# V0p2_Main_PCB2.net
KiCad netlist of a schematic drawn in EAGLE
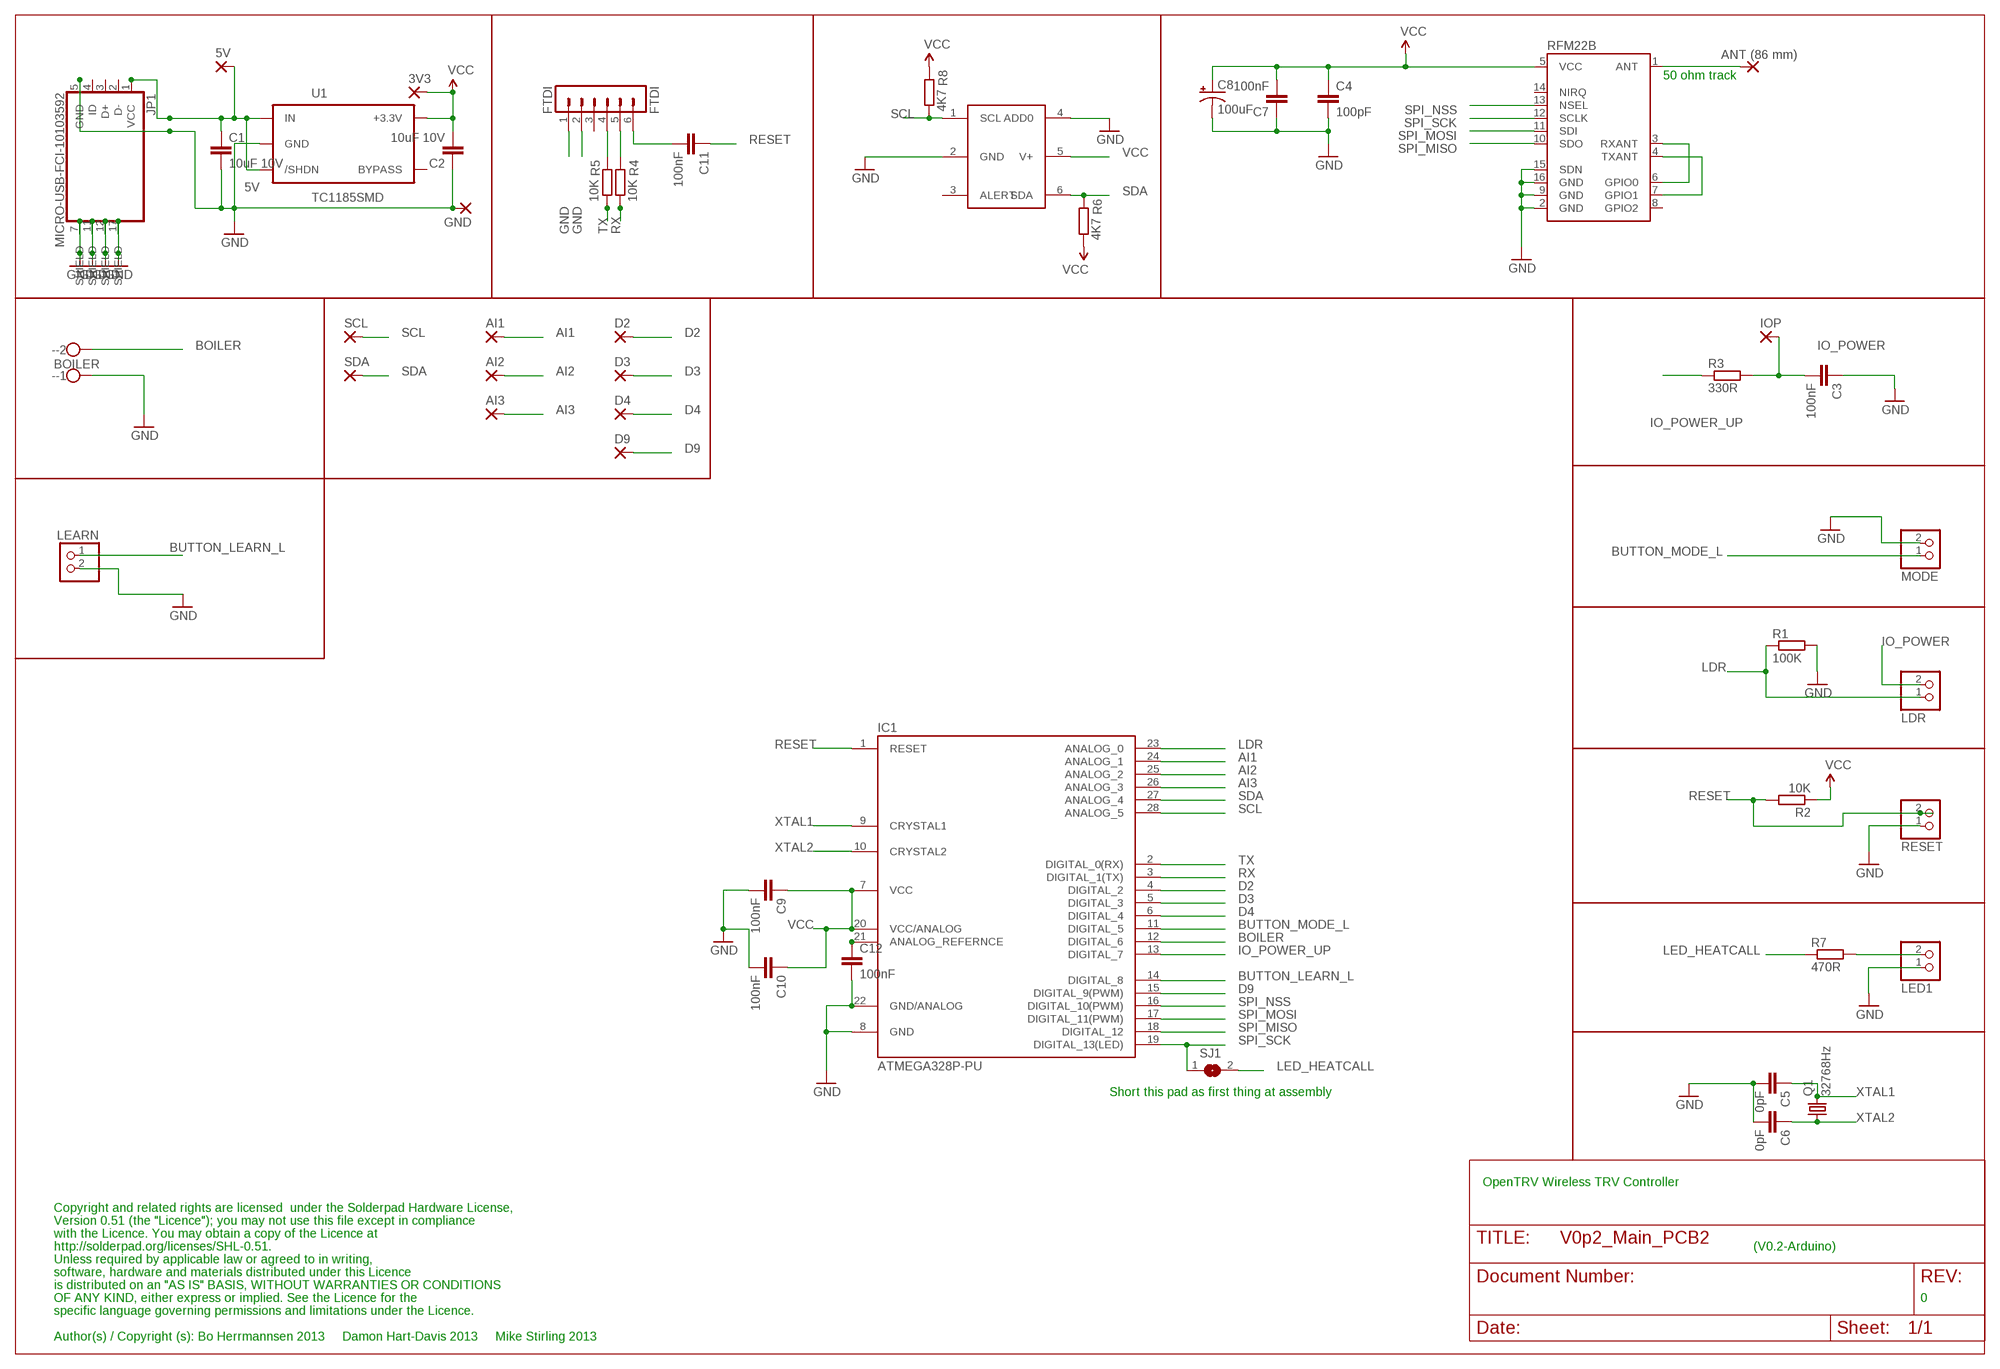
[diagram p0: schematic, sheet 1]

(export (version "E")
  (design (tool "Eeschema 10.0.6"))
  (components
    (comp (ref "-")
      (value "BOILER")
      (footprint "eagle-import:SCREWTERMINAL")
      (fields (field (name "MPN") "237-102"))
      (libsource (lib "eagle-import") (part "W237-102"))
    )
    (comp (ref "3V3")
      (value "2,15/1,0")
      (footprint "eagle-import:2,15_1,0")
      (libsource (lib "eagle-import") (part "2,15/1,0"))
    )
    (comp (ref "5V")
      (value "2,15/1,0")
      (footprint "eagle-import:2,15_1,0")
      (libsource (lib "eagle-import") (part "2,15/1,0"))
    )
    (comp (ref "AI1")
      (value "2,15/1,0")
      (footprint "eagle-import:2,15_1,0")
      (libsource (lib "eagle-import") (part "2,15/1,0"))
    )
    (comp (ref "AI2")
      (value "2,15/1,0")
      (footprint "eagle-import:2,15_1,0")
      (libsource (lib "eagle-import") (part "2,15/1,0"))
    )
    (comp (ref "AI3")
      (value "2,15/1,0")
      (footprint "eagle-import:2,15_1,0")
      (libsource (lib "eagle-import") (part "2,15/1,0"))
    )
    (comp (ref "ANT")
      (value "ANT (86 mm)")
      (footprint "eagle-import:2,15_1,0")
      (libsource (lib "eagle-import") (part "2,15/1,0"))
    )
    (comp (ref "C1")
      (value "10uF 10V")
      (footprint "eagle-import:0603-CAP")
      (libsource (lib "eagle-import") (part "CAP0603-CAP"))
    )
    (comp (ref "C2")
      (value "10uF 10V")
      (footprint "eagle-import:0603-CAP")
      (libsource (lib "eagle-import") (part "CAP0603-CAP"))
    )
    (comp (ref "C3")
      (value "100nF")
      (footprint "eagle-import:0603-CAP")
      (libsource (lib "eagle-import") (part "CAP0603-CAP"))
    )
    (comp (ref "C4")
      (value "100pF")
      (footprint "eagle-import:0603-CAP")
      (libsource (lib "eagle-import") (part "CAP0603-CAP"))
    )
    (comp (ref "C5")
      (value "0pF")
      (footprint "eagle-import:0603-CAP")
      (libsource (lib "eagle-import") (part "CAP0603-CAP"))
    )
    (comp (ref "C6")
      (value "0pF")
      (footprint "eagle-import:0603-CAP")
      (libsource (lib "eagle-import") (part "CAP0603-CAP"))
    )
    (comp (ref "C7")
      (value "100nF")
      (footprint "eagle-import:0603-CAP")
      (libsource (lib "eagle-import") (part "CAP0603-CAP"))
    )
    (comp (ref "C8")
      (value "100uF")
      (footprint "eagle-import:EIA3216")
      (libsource (lib "eagle-import") (part "CAP_POL1206"))
    )
    (comp (ref "C9")
      (value "100nF")
      (footprint "eagle-import:0603-CAP")
      (libsource (lib "eagle-import") (part "CAP0603-CAP"))
    )
    (comp (ref "C10")
      (value "100nF")
      (footprint "eagle-import:0603-CAP")
      (libsource (lib "eagle-import") (part "CAP0603-CAP"))
    )
    (comp (ref "C11")
      (value "100nF")
      (footprint "eagle-import:0603-CAP")
      (libsource (lib "eagle-import") (part "CAP0603-CAP"))
    )
    (comp (ref "C12")
      (value "100nF")
      (footprint "eagle-import:0603-CAP")
      (libsource (lib "eagle-import") (part "CAP0603-CAP"))
    )
    (comp (ref "D2")
      (value "2,15/1,0")
      (footprint "eagle-import:2,15_1,0")
      (libsource (lib "eagle-import") (part "2,15/1,0"))
    )
    (comp (ref "D3")
      (value "2,15/1,0")
      (footprint "eagle-import:2,15_1,0")
      (libsource (lib "eagle-import") (part "2,15/1,0"))
    )
    (comp (ref "D4")
      (value "2,15/1,0")
      (footprint "eagle-import:2,15_1,0")
      (libsource (lib "eagle-import") (part "2,15/1,0"))
    )
    (comp (ref "D9")
      (value "2,15/1,0")
      (footprint "eagle-import:2,15_1,0")
      (libsource (lib "eagle-import") (part "2,15/1,0"))
    )
    (comp (ref "FTDI")
      (value "FTDI")
      (footprint "eagle-import:MA06-1")
      (libsource (lib "eagle-import") (part "MA06-1"))
    )
    (comp (ref "GND")
      (value "2,15/1,0")
      (footprint "eagle-import:2,15_1,0")
      (libsource (lib "eagle-import") (part "2,15/1,0"))
    )
    (comp (ref "IC1")
      (value "ATMEGA328P-PU")
      (footprint "eagle-import:DIL28-3")
      (libsource (lib "eagle-import") (part "ATMEGA8-PU"))
    )
    (comp (ref "IOP")
      (value "2,15/1,0")
      (footprint "eagle-import:2,15_1,0")
      (libsource (lib "eagle-import") (part "2,15/1,0"))
    )
    (comp (ref "JP1")
      (value "MICRO-USB-FCI-10103592")
      (footprint "eagle-import:MICRO-USB-FCI-10103592")
      (libsource (lib "eagle-import") (part "MICRO-USB-FCI-10103592"))
    )
    (comp (ref "LDR")
      (value "PINHD-1X2")
      (footprint "eagle-import:1X02")
      (libsource (lib "eagle-import") (part "PINHD-1X2"))
    )
    (comp (ref "LEARN")
      (value "PINHD-1X2")
      (footprint "eagle-import:1X02")
      (libsource (lib "eagle-import") (part "PINHD-1X2"))
    )
    (comp (ref "LED1")
      (value "PINHD-1X2")
      (footprint "eagle-import:1X02")
      (libsource (lib "eagle-import") (part "PINHD-1X2"))
    )
    (comp (ref "MODE")
      (value "PINHD-1X2")
      (footprint "eagle-import:1X02")
      (libsource (lib "eagle-import") (part "PINHD-1X2"))
    )
    (comp (ref "Q1")
      (value "32768Hz")
      (footprint "eagle-import:MC-306")
      (fields (field (name "MPN") "MC-306 60.0KHZ  100PPM ,12.5PF"))
      (libsource (lib "eagle-import") (part "MC-306"))
    )
    (comp (ref "R1")
      (value "100K")
      (footprint "eagle-import:R0603")
      (libsource (lib "eagle-import") (part "R-EU_R0603"))
    )
    (comp (ref "R2")
      (value "10K")
      (footprint "eagle-import:R0603")
      (libsource (lib "eagle-import") (part "R-EU_R0603"))
    )
    (comp (ref "R3")
      (value "330R")
      (footprint "eagle-import:R0603")
      (libsource (lib "eagle-import") (part "R-EU_R0603"))
    )
    (comp (ref "R4")
      (value "10K")
      (footprint "eagle-import:R0603")
      (libsource (lib "eagle-import") (part "R-EU_R0603"))
    )
    (comp (ref "R5")
      (value "10K")
      (footprint "eagle-import:R0603")
      (libsource (lib "eagle-import") (part "R-EU_R0603"))
    )
    (comp (ref "R6")
      (value "4K7")
      (footprint "eagle-import:R0603")
      (libsource (lib "eagle-import") (part "R-EU_R0603"))
    )
    (comp (ref "R7")
      (value "470R")
      (footprint "eagle-import:R0603")
      (libsource (lib "eagle-import") (part "R-EU_R0603"))
    )
    (comp (ref "R8")
      (value "4K7")
      (footprint "eagle-import:R0603")
      (libsource (lib "eagle-import") (part "R-EU_R0603"))
    )
    (comp (ref "RESET")
      (value "PINHD-1X2")
      (footprint "eagle-import:1X02")
      (libsource (lib "eagle-import") (part "PINHD-1X2"))
    )
    (comp (ref "RFM22B")
      (value "RFM22SMD")
      (footprint "eagle-import:RFM22-XXX-S2")
      (libsource (lib "eagle-import") (part "RFM22SMD"))
    )
    (comp (ref "SCL")
      (value "2,15/1,0")
      (footprint "eagle-import:2,15_1,0")
      (libsource (lib "eagle-import") (part "2,15/1,0"))
    )
    (comp (ref "SDA")
      (value "2,15/1,0")
      (footprint "eagle-import:2,15_1,0")
      (libsource (lib "eagle-import") (part "2,15/1,0"))
    )
    (comp (ref "SJ1") (value "SJ") (footprint "eagle-import:SJ") (libsource (lib "eagle-import") (part "SJ")))
    (comp (ref "TMP")
      (value "TMP112")
      (footprint "eagle-import:TMP112")
      (libsource (lib "eagle-import") (part "TMP112"))
    )
    (comp (ref "U1")
      (value "TC1185SMD")
      (footprint "eagle-import:TC1185")
      (libsource (lib "eagle-import") (part "TC1185SMD"))
    )
  )
  (nets
    (net (code "1") (name "/5V") (class "Default")
      (node (ref "5V") (pin "1") (pinfunction "P_1") (pintype "passive"))
      (node (ref "C1") (pin "1") (pinfunction "1_1") (pintype "passive"))
      (node (ref "JP1") (pin "1") (pinfunction "VCC_1") (pintype "bidirectional"))
      (node (ref "U1") (pin "1") (pinfunction "IN_1") (pintype "passive"))
      (node (ref "U1") (pin "3") (pinfunction "/SHDN_3") (pintype "passive"))
    )
    (net (code "2") (name "/AI1") (class "Default")
      (node (ref "AI1") (pin "1") (pinfunction "P_1") (pintype "passive"))
      (node (ref "IC1") (pin "24") (pinfunction "ANALOG_1_24") (pintype "bidirectional"))
    )
    (net (code "3") (name "/AI2") (class "Default")
      (node (ref "AI2") (pin "1") (pinfunction "P_1") (pintype "passive"))
      (node (ref "IC1") (pin "25") (pinfunction "ANALOG_2_25") (pintype "bidirectional"))
    )
    (net (code "4") (name "/AI3") (class "Default")
      (node (ref "AI3") (pin "1") (pinfunction "P_1") (pintype "passive"))
      (node (ref "IC1") (pin "26") (pinfunction "ANALOG_3_26") (pintype "bidirectional"))
    )
    (net (code "5") (name "/BOILER") (class "Default")
      (node (ref "-") (pin "2") (pinfunction "KL_2") (pintype "passive"))
      (node (ref "IC1") (pin "12") (pinfunction "DIGITAL_6_12") (pintype "bidirectional"))
    )
    (net (code "6") (name "/BUTTON_LEARN_L") (class "Default")
      (node (ref "IC1") (pin "14") (pinfunction "DIGITAL_8_14") (pintype "bidirectional"))
      (node (ref "LEARN") (pin "1") (pinfunction "1_1") (pintype "passive"))
    )
    (net (code "7") (name "/BUTTON_MODE_L") (class "Default")
      (node (ref "IC1") (pin "11") (pinfunction "DIGITAL_5_11") (pintype "bidirectional"))
      (node (ref "MODE") (pin "1") (pinfunction "1_1") (pintype "passive"))
    )
    (net (code "8") (name "/D2") (class "Default")
      (node (ref "D2") (pin "1") (pinfunction "P_1") (pintype "passive"))
      (node (ref "IC1") (pin "4") (pinfunction "DIGITAL_2_4") (pintype "bidirectional"))
    )
    (net (code "9") (name "/D3") (class "Default")
      (node (ref "D3") (pin "1") (pinfunction "P_1") (pintype "passive"))
      (node (ref "IC1") (pin "5") (pinfunction "DIGITAL_3_5") (pintype "bidirectional"))
    )
    (net (code "10") (name "/D4") (class "Default")
      (node (ref "D4") (pin "1") (pinfunction "P_1") (pintype "passive"))
      (node (ref "IC1") (pin "6") (pinfunction "DIGITAL_4_6") (pintype "bidirectional"))
    )
    (net (code "11") (name "/D9") (class "Default")
      (node (ref "D9") (pin "1") (pinfunction "P_1") (pintype "passive"))
      (node (ref "IC1") (pin "15") (pinfunction "DIGITAL_9(PWM)_15") (pintype "bidirectional"))
    )
    (net (code "12") (name "/IO_POWER") (class "Default")
      (node (ref "C3") (pin "2") (pinfunction "2_2") (pintype "passive"))
      (node (ref "IOP") (pin "1") (pinfunction "P_1") (pintype "passive"))
      (node (ref "LDR") (pin "2") (pinfunction "2_2") (pintype "passive"))
      (node (ref "R3") (pin "2") (pinfunction "2_2") (pintype "passive"))
    )
    (net (code "13") (name "/IO_POWER_UP") (class "Default")
      (node (ref "IC1") (pin "13") (pinfunction "DIGITAL_7_13") (pintype "bidirectional"))
      (node (ref "R3") (pin "1") (pinfunction "1_1") (pintype "passive"))
    )
    (net (code "14") (name "/LDR") (class "Default")
      (node (ref "IC1") (pin "23") (pinfunction "ANALOG_0_23") (pintype "bidirectional"))
      (node (ref "LDR") (pin "1") (pinfunction "1_1") (pintype "passive"))
      (node (ref "R1") (pin "1") (pinfunction "1_1") (pintype "passive"))
    )
    (net (code "15") (name "/LED_HEATCALL") (class "Default")
      (node (ref "R7") (pin "1") (pinfunction "1_1") (pintype "passive"))
      (node (ref "SJ1") (pin "2") (pinfunction "2_2") (pintype "passive"))
    )
    (net (code "16") (name "/RESET") (class "Default")
      (node (ref "C11") (pin "1") (pinfunction "1_1") (pintype "passive"))
      (node (ref "IC1") (pin "1") (pinfunction "RESET_1") (pintype "bidirectional"))
      (node (ref "R2") (pin "2") (pinfunction "2_2") (pintype "passive"))
      (node (ref "RESET") (pin "2") (pinfunction "2_2") (pintype "passive"))
    )
    (net (code "17") (name "/RX") (class "Default")
      (node (ref "IC1") (pin "3") (pinfunction "DIGITAL_1(TX)_3") (pintype "bidirectional"))
      (node (ref "R4") (pin "1") (pinfunction "1_1") (pintype "passive"))
    )
    (net (code "18") (name "/SCL") (class "Default")
      (node (ref "IC1") (pin "28") (pinfunction "ANALOG_5_28") (pintype "bidirectional"))
      (node (ref "R8") (pin "1") (pinfunction "1_1") (pintype "passive"))
      (node (ref "SCL") (pin "1") (pinfunction "P_1") (pintype "passive"))
      (node (ref "TMP") (pin "1") (pinfunction "SCL_1") (pintype "bidirectional"))
    )
    (net (code "19") (name "/SDA") (class "Default")
      (node (ref "IC1") (pin "27") (pinfunction "ANALOG_4_27") (pintype "bidirectional"))
      (node (ref "R6") (pin "2") (pinfunction "2_2") (pintype "passive"))
      (node (ref "SDA") (pin "1") (pinfunction "P_1") (pintype "passive"))
      (node (ref "TMP") (pin "6") (pinfunction "SDA_6") (pintype "bidirectional"))
    )
    (net (code "20") (name "/SPI_MISO") (class "Default")
      (node (ref "IC1") (pin "18") (pinfunction "DIGITAL_12_18") (pintype "bidirectional"))
      (node (ref "RFM22B") (pin "10") (pinfunction "SDO_10") (pintype "output"))
    )
    (net (code "21") (name "/SPI_MOSI") (class "Default")
      (node (ref "IC1") (pin "17") (pinfunction "DIGITAL_11(PWM)_17") (pintype "bidirectional"))
      (node (ref "RFM22B") (pin "11") (pinfunction "SDI_11") (pintype "input"))
    )
    (net (code "22") (name "/SPI_NSS") (class "Default")
      (node (ref "IC1") (pin "16") (pinfunction "DIGITAL_10(PWM)_16") (pintype "bidirectional"))
      (node (ref "RFM22B") (pin "13") (pinfunction "NSEL_13") (pintype "input"))
    )
    (net (code "23") (name "/SPI_SCK") (class "Default")
      (node (ref "IC1") (pin "19") (pinfunction "DIGITAL_13(LED)_19") (pintype "bidirectional"))
      (node (ref "RFM22B") (pin "12") (pinfunction "SCLK_12") (pintype "input"))
      (node (ref "SJ1") (pin "1") (pinfunction "1_1") (pintype "passive"))
    )
    (net (code "24") (name "/TX") (class "Default")
      (node (ref "IC1") (pin "2") (pinfunction "DIGITAL_0(RX)_2") (pintype "bidirectional"))
      (node (ref "R5") (pin "1") (pinfunction "1_1") (pintype "passive"))
    )
    (net (code "25") (name "/XTAL1") (class "Default")
      (node (ref "C5") (pin "1") (pinfunction "1_1") (pintype "passive"))
      (node (ref "IC1") (pin "9") (pinfunction "CRYSTAL1_9") (pintype "bidirectional"))
      (node (ref "Q1") (pin "4") (pinfunction "2_4") (pintype "passive"))
    )
    (net (code "26") (name "/XTAL2") (class "Default")
      (node (ref "C6") (pin "1") (pinfunction "1_1") (pintype "passive"))
      (node (ref "IC1") (pin "10") (pinfunction "CRYSTAL2_10") (pintype "bidirectional"))
      (node (ref "Q1") (pin "1") (pinfunction "1_1") (pintype "passive"))
    )
    (net (code "27") (name "GND") (class "Default")
      (node (ref "-") (pin "1") (pinfunction "KL_1") (pintype "passive"))
      (node (ref "C1") (pin "2") (pinfunction "2_2") (pintype "passive"))
      (node (ref "C10") (pin "2") (pinfunction "2_2") (pintype "passive"))
      (node (ref "C12") (pin "2") (pinfunction "2_2") (pintype "passive"))
      (node (ref "C2") (pin "1") (pinfunction "1_1") (pintype "passive"))
      (node (ref "C3") (pin "1") (pinfunction "1_1") (pintype "passive"))
      (node (ref "C4") (pin "2") (pinfunction "2_2") (pintype "passive"))
      (node (ref "C5") (pin "2") (pinfunction "2_2") (pintype "passive"))
      (node (ref "C6") (pin "2") (pinfunction "2_2") (pintype "passive"))
      (node (ref "C7") (pin "1") (pinfunction "1_1") (pintype "passive"))
      (node (ref "C8") (pin "C") (pinfunction "-_C") (pintype "passive"))
      (node (ref "C9") (pin "2") (pinfunction "2_2") (pintype "passive"))
      (node (ref "FTDI") (pin "1") (pinfunction "GND_1") (pintype "passive"))
      (node (ref "FTDI") (pin "2") (pinfunction "CTS_2") (pintype "passive"))
      (node (ref "GND") (pin "1") (pinfunction "P_1") (pintype "passive"))
      (node (ref "IC1") (pin "22") (pinfunction "GND/ANALOG_22") (pintype "power_in"))
      (node (ref "IC1") (pin "8") (pinfunction "GND_8") (pintype "power_in"))
      (node (ref "JP1") (pin "11") (pinfunction "SHIELD_11") (pintype "bidirectional"))
      (node (ref "JP1") (pin "12") (pinfunction "SHIELD_12") (pintype "bidirectional"))
      (node (ref "JP1") (pin "17") (pinfunction "SHIELD_17") (pintype "bidirectional"))
      (node (ref "JP1") (pin "5") (pinfunction "GND_5") (pintype "bidirectional"))
      (node (ref "JP1") (pin "7") (pinfunction "SHIELD_7") (pintype "bidirectional"))
      (node (ref "LEARN") (pin "2") (pinfunction "2_2") (pintype "passive"))
      (node (ref "LED1") (pin "1") (pinfunction "1_1") (pintype "passive"))
      (node (ref "MODE") (pin "2") (pinfunction "2_2") (pintype "passive"))
      (node (ref "R1") (pin "2") (pinfunction "2_2") (pintype "passive"))
      (node (ref "RESET") (pin "1") (pinfunction "1_1") (pintype "passive"))
      (node (ref "RFM22B") (pin "15") (pinfunction "SDN_15") (pintype "input"))
      (node (ref "RFM22B") (pin "16") (pinfunction "GND_16") (pintype "power_in"))
      (node (ref "RFM22B") (pin "2") (pinfunction "GND_2") (pintype "power_in"))
      (node (ref "RFM22B") (pin "9") (pinfunction "GND_9") (pintype "power_in"))
      (node (ref "TMP") (pin "2") (pinfunction "GND_2") (pintype "bidirectional"))
      (node (ref "TMP") (pin "4") (pinfunction "ADD0_4") (pintype "bidirectional"))
      (node (ref "U1") (pin "2") (pinfunction "GND_2") (pintype "passive"))
    )
    (net (code "28") (name "Net-(ANT-P)") (class "Default")
      (node (ref "ANT") (pin "1") (pinfunction "P_1") (pintype "passive"))
      (node (ref "RFM22B") (pin "1") (pinfunction "ANT_1") (pintype "bidirectional"))
    )
    (net (code "29") (name "Net-(FTDI-RTS)") (class "Default")
      (node (ref "C11") (pin "2") (pinfunction "2_2") (pintype "passive"))
      (node (ref "FTDI") (pin "6") (pinfunction "RTS_6") (pintype "passive"))
    )
    (net (code "30") (name "Net-(FTDI-RX)") (class "Default")
      (node (ref "FTDI") (pin "5") (pinfunction "RX_5") (pintype "passive"))
      (node (ref "R4") (pin "2") (pinfunction "2_2") (pintype "passive"))
    )
    (net (code "31") (name "Net-(FTDI-TX)") (class "Default")
      (node (ref "FTDI") (pin "4") (pinfunction "TX_4") (pintype "passive"))
      (node (ref "R5") (pin "2") (pinfunction "2_2") (pintype "passive"))
    )
    (net (code "32") (name "Net-(IC1-ANALOG_REFERNCE)") (class "Default")
      (node (ref "C12") (pin "1") (pinfunction "1_1") (pintype "passive"))
      (node (ref "IC1") (pin "21") (pinfunction "ANALOG_REFERNCE_21") (pintype "passive"))
    )
    (net (code "33") (name "Net-(LED1-Pad2)") (class "Default")
      (node (ref "LED1") (pin "2") (pinfunction "2_2") (pintype "passive"))
      (node (ref "R7") (pin "2") (pinfunction "2_2") (pintype "passive"))
    )
    (net (code "34") (name "Net-(RFM22B-GPIO0)") (class "Default")
      (node (ref "RFM22B") (pin "3") (pinfunction "RXANT_3") (pintype "input"))
      (node (ref "RFM22B") (pin "6") (pinfunction "GPIO0_6") (pintype "bidirectional"))
    )
    (net (code "35") (name "Net-(RFM22B-GPIO1)") (class "Default")
      (node (ref "RFM22B") (pin "4") (pinfunction "TXANT_4") (pintype "input"))
      (node (ref "RFM22B") (pin "7") (pinfunction "GPIO1_7") (pintype "bidirectional"))
    )
    (net (code "36") (name "VCC") (class "Default")
      (node (ref "3V3") (pin "1") (pinfunction "P_1") (pintype "passive"))
      (node (ref "C10") (pin "1") (pinfunction "1_1") (pintype "passive"))
      (node (ref "C2") (pin "2") (pinfunction "2_2") (pintype "passive"))
      (node (ref "C4") (pin "1") (pinfunction "1_1") (pintype "passive"))
      (node (ref "C7") (pin "2") (pinfunction "2_2") (pintype "passive"))
      (node (ref "C8") (pin "A") (pinfunction "+_A") (pintype "passive"))
      (node (ref "C9") (pin "1") (pinfunction "1_1") (pintype "passive"))
      (node (ref "IC1") (pin "20") (pinfunction "VCC/ANALOG_20") (pintype "passive"))
      (node (ref "IC1") (pin "7") (pinfunction "VCC_7") (pintype "power_in"))
      (node (ref "R2") (pin "1") (pinfunction "1_1") (pintype "passive"))
      (node (ref "R6") (pin "1") (pinfunction "1_1") (pintype "passive"))
      (node (ref "R8") (pin "2") (pinfunction "2_2") (pintype "passive"))
      (node (ref "RFM22B") (pin "5") (pinfunction "VCC_5") (pintype "bidirectional"))
      (node (ref "TMP") (pin "5") (pinfunction "V+_5") (pintype "bidirectional"))
      (node (ref "U1") (pin "5") (pinfunction "+3.3V_5") (pintype "power_in"))
    )
    (net (code "37") (name "unconnected-(FTDI-VCC-Pad3)") (class "Default")
      (node (ref "FTDI") (pin "3") (pinfunction "VCC_3") (pintype "passive"))
    )
    (net (code "38") (name "unconnected-(JP1-D+-Pad3)") (class "Default")
      (node (ref "JP1") (pin "3") (pinfunction "D+_3") (pintype "bidirectional"))
    )
    (net (code "39") (name "unconnected-(JP1-D--Pad2)") (class "Default")
      (node (ref "JP1") (pin "2") (pinfunction "D-_2") (pintype "bidirectional"))
    )
    (net (code "40") (name "unconnected-(JP1-ID-Pad4)") (class "Default")
      (node (ref "JP1") (pin "4") (pinfunction "ID_4") (pintype "bidirectional"))
    )
    (net (code "41") (name "unconnected-(RFM22B-GPIO2-Pad8)") (class "Default")
      (node (ref "RFM22B") (pin "8") (pinfunction "GPIO2_8") (pintype "bidirectional"))
    )
    (net (code "42") (name "unconnected-(RFM22B-NIRQ-Pad14)") (class "Default")
      (node (ref "RFM22B") (pin "14") (pinfunction "NIRQ_14") (pintype "output"))
    )
    (net (code "43") (name "unconnected-(TMP-ALERT-Pad3)") (class "Default")
      (node (ref "TMP") (pin "3") (pinfunction "ALERT_3") (pintype "bidirectional"))
    )
    (net (code "44") (name "unconnected-(U1-BYPASS-Pad4)") (class "Default")
      (node (ref "U1") (pin "4") (pinfunction "BYPASS_4") (pintype "passive"))
    )
  )
)
